# rev02_11.net
KiCad netlist of a schematic drawn in Altium Designer
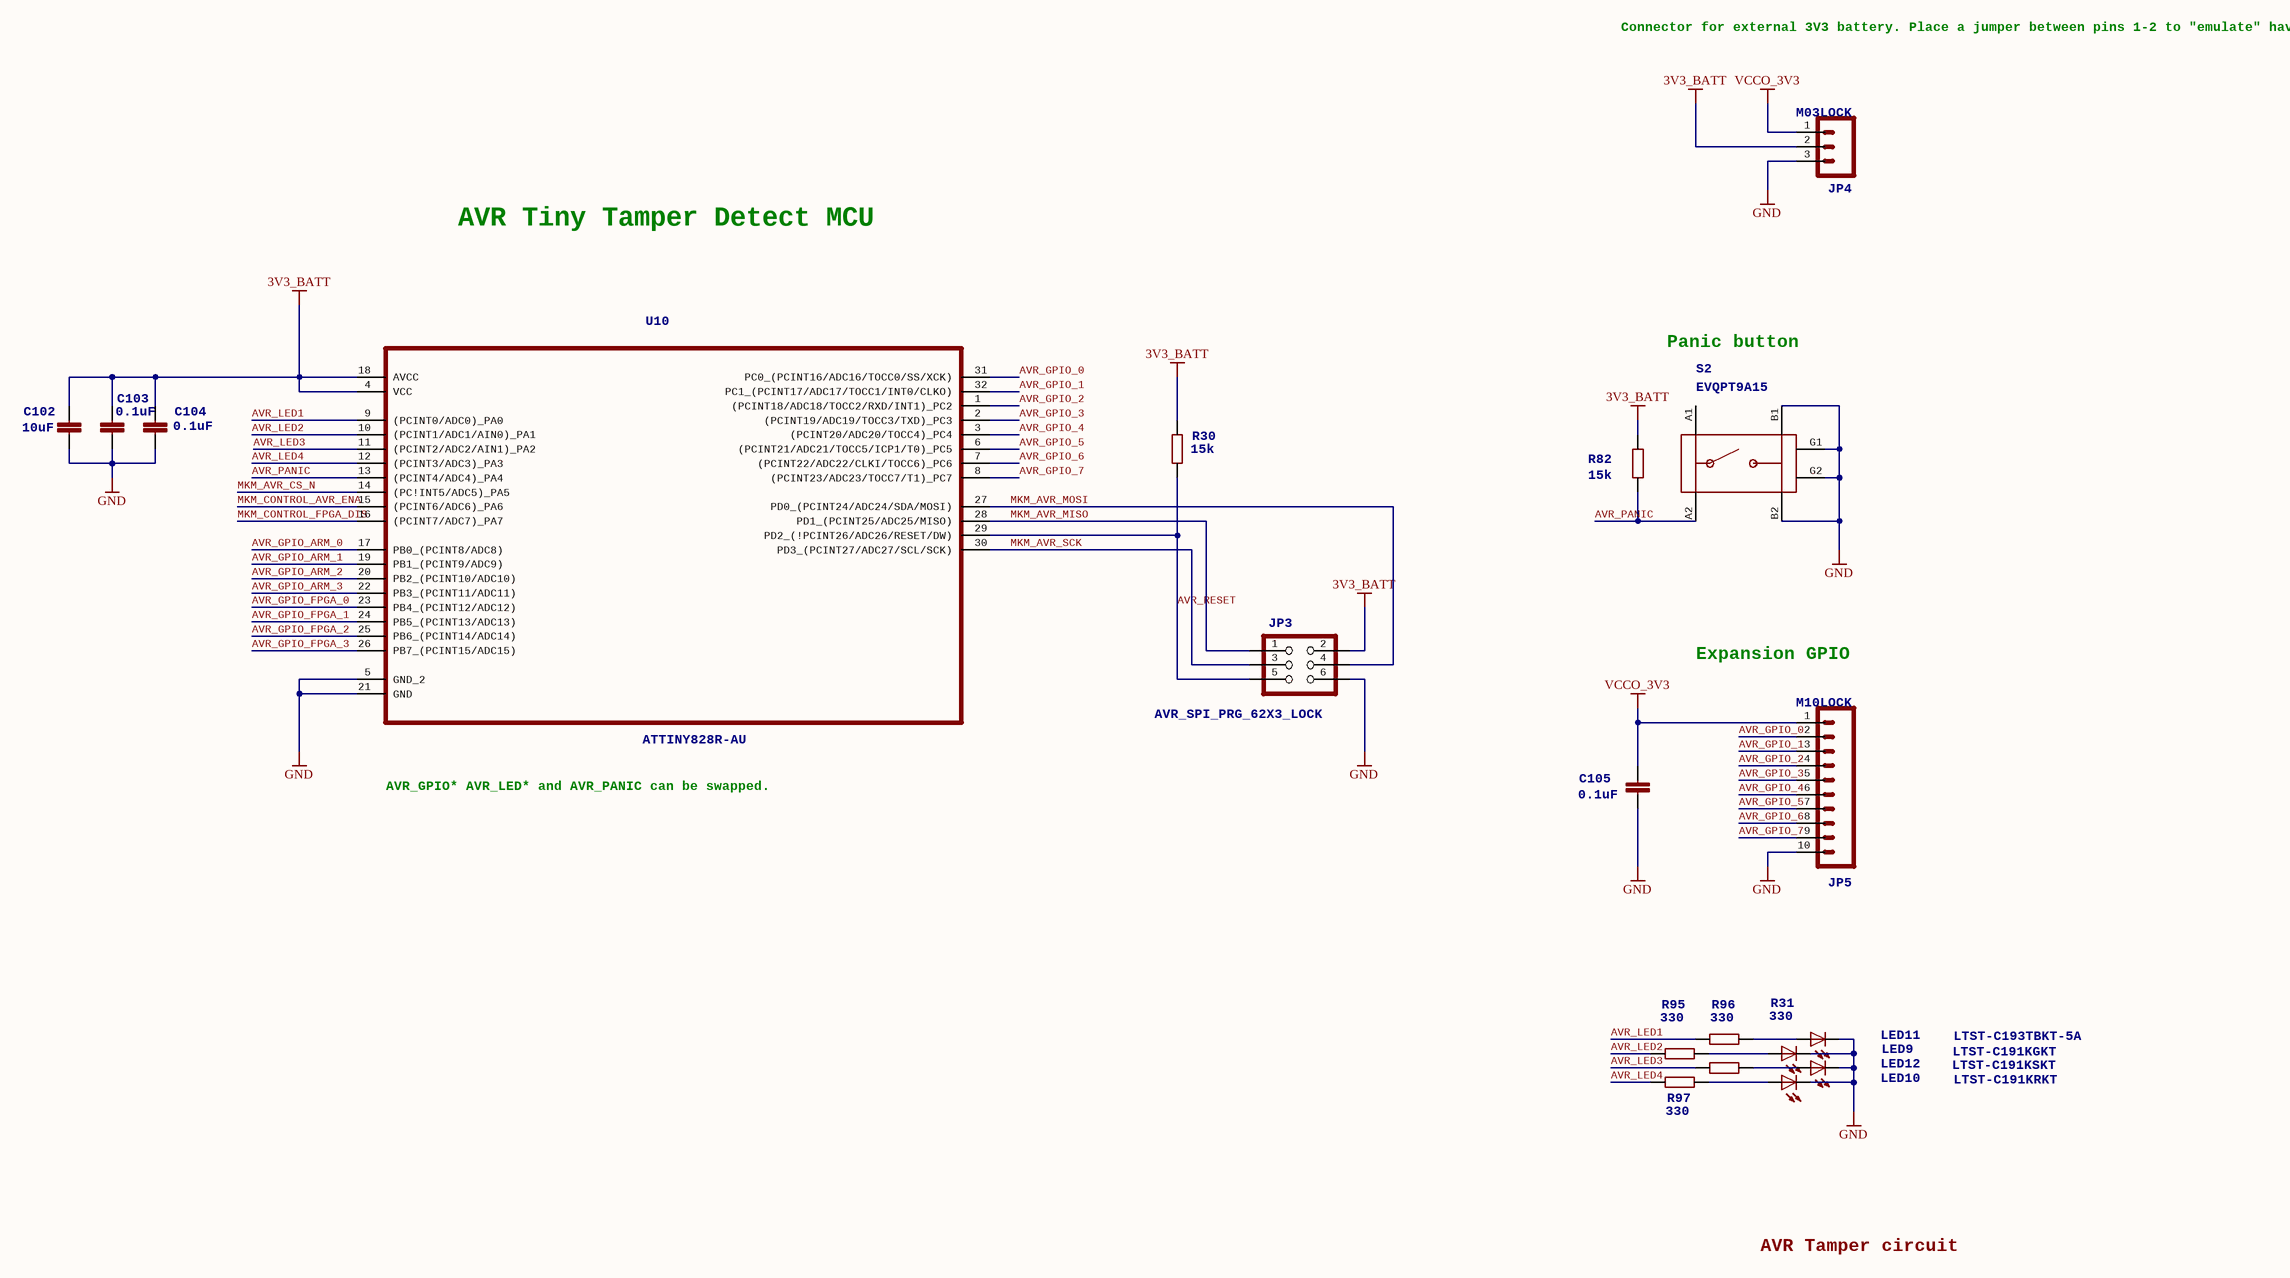
[diagram p0: rev02_11.SchDoc]

(export (version "E")
  (design (tool "Eeschema 10.0.6"))
  (components
    (comp (ref "C102")
      (value "10uF")
      (footprint "C_0805")
      (description "0805 CAPACITOR")
      (libsource (lib "resistor") (part "C-EUC0805"))
    )
    (comp (ref "C103")
      (value "0.1uF")
      (footprint "C_0402")
      (description "0402 CAPACITOR")
      (libsource (lib "resistor") (part "C-EUC0402"))
    )
    (comp (ref "C104")
      (value "0.1uF")
      (footprint "C_0402")
      (description "0402 CAPACITOR")
      (libsource (lib "resistor") (part "C-EUC0402"))
    )
    (comp (ref "C105")
      (value "0.1uF")
      (footprint "C_0402")
      (description "0402 CAPACITOR")
      (libsource (lib "resistor") (part "C-EUC0402"))
    )
    (comp (ref "JP3")
      (value "AVR_SPI_PRG_62X3_LOCK")
      (footprint "PLD-6")
      (libsource (lib "SparkFun-Connectors") (part "AVR_SPI_PRG_62X3_LOCK"))
    )
    (comp (ref "JP4")
      (value "M03LOCK")
      (footprint "PLS-3")
      (fields (field (name ">VALUE") "M03LOCK") (field (name ">NAME") "JP4"))
      (libsource (lib "SparkFun-Connectors") (part "M03LOCK"))
    )
    (comp (ref "JP5")
      (value "M10LOCK")
      (footprint "HDR1X10")
      (fields (field (name ">VALUE") "M10LOCK") (field (name ">NAME") "JP5"))
      (libsource (lib "SparkFun-Connectors") (part "M10LOCK"))
    )
    (comp (ref "LED9")
      (value "LTST-C191KGKT")
      (footprint "VD_0603")
      (description "GREEN LED")
      (libsource (lib "rev02_1") (part "LEDCHIP-LED0603"))
    )
    (comp (ref "LED10")
      (value "LTST-C191KRKT")
      (footprint "VD_0603")
      (description "RED LED")
      (libsource (lib "rev02_1") (part "LEDCHIP-LED0603"))
    )
    (comp (ref "LED11")
      (value "LTST-C193TBKT-5A")
      (footprint "VD_0603")
      (description "BLUE LED")
      (libsource (lib "rev02_1") (part "LEDCHIP-LED0603"))
    )
    (comp (ref "LED12")
      (value "LTST-C191KSKT")
      (footprint "VD_0603")
      (description "YELLOW LED")
      (libsource (lib "rev02_1") (part "LEDCHIP-LED0603"))
    )
    (comp (ref "R30")
      (value "15k")
      (footprint "R_0402")
      (description "0402 Resistor 5%")
      (fields (field (name ">NAME") "R30"))
      (libsource (lib "resistor") (part "R-EU_R0402"))
    )
    (comp (ref "R31")
      (value "330")
      (footprint "R_0402")
      (description "0402 Resistor 5%")
      (libsource (lib "resistor") (part "R-EU_R0402"))
    )
    (comp (ref "R82")
      (value "15k")
      (footprint "R_0402")
      (description "0402 Resistor 5%")
      (libsource (lib "resistor") (part "R-EU_R0402"))
    )
    (comp (ref "R95")
      (value "330")
      (footprint "R_0402")
      (description "0402 Resistor 5%")
      (libsource (lib "resistor") (part "R-EU_R0402"))
    )
    (comp (ref "R96")
      (value "330")
      (footprint "R_0402")
      (description "0402 Resistor 5%")
      (libsource (lib "resistor") (part "R-EU_R0402"))
    )
    (comp (ref "R97")
      (value "330")
      (footprint "R_0402")
      (description "0402 Resistor 5%")
      (libsource (lib "resistor") (part "R-EU_R0402"))
    )
    (comp (ref "S2")
      (value "EVQPT9A15")
      (footprint "TACTILE_SWITCH")
      (description "Tacktile switch")
      (fields (field (name ">NAME") "S2"))
      (libsource (lib "UsedComponents") (part "TACTILE_SWITCH"))
    )
    (comp (ref "U10")
      (value "ATTINY828R-AU")
      (footprint "LQFP-32")
      (description "IC, MCU, 8KB, FLASH, 20MHZ, TQFP-32")
      (fields (field (name ">NAME") "U10") (field (name ">VALUE") "ATTINY828R-AU"))
      (libsource (lib "ATMEL-ATTINY828R-AU") (part "ATTINY828R-AU"))
    )
  )
  (nets
    (net (code "1") (name "/AVR_GPIO_0") (class "Default")
      (node (ref "JP5") (pin "2") (pinfunction "2_2") (pintype "passive"))
      (node (ref "U10") (pin "31") (pinfunction "PC0_(PCINT16/ADC16/TOCC0/SS/XCK)_31") (pintype "passive"))
    )
    (net (code "2") (name "/AVR_GPIO_1") (class "Default")
      (node (ref "JP5") (pin "3") (pinfunction "3_3") (pintype "passive"))
      (node (ref "U10") (pin "32") (pinfunction "PC1_(PCINT17/ADC17/TOCC1/INT0/CLKO)_32") (pintype "passive"))
    )
    (net (code "3") (name "/AVR_GPIO_2") (class "Default")
      (node (ref "JP5") (pin "4") (pinfunction "4_4") (pintype "passive"))
      (node (ref "U10") (pin "1") (pinfunction "(PCINT18/ADC18/TOCC2/RXD/INT1)_PC2_1") (pintype "passive"))
    )
    (net (code "4") (name "/AVR_GPIO_3") (class "Default")
      (node (ref "JP5") (pin "5") (pinfunction "5_5") (pintype "passive"))
      (node (ref "U10") (pin "2") (pinfunction "(PCINT19/ADC19/TOCC3/TXD)_PC3_2") (pintype "passive"))
    )
    (net (code "5") (name "/AVR_GPIO_4") (class "Default")
      (node (ref "JP5") (pin "6") (pinfunction "6_6") (pintype "passive"))
      (node (ref "U10") (pin "3") (pinfunction "(PCINT20/ADC20/TOCC4)_PC4_3") (pintype "passive"))
    )
    (net (code "6") (name "/AVR_GPIO_5") (class "Default")
      (node (ref "JP5") (pin "7") (pinfunction "7_7") (pintype "passive"))
      (node (ref "U10") (pin "6") (pinfunction "(PCINT21/ADC21/TOCC5/ICP1/T0)_PC5_6") (pintype "passive"))
    )
    (net (code "7") (name "/AVR_GPIO_6") (class "Default")
      (node (ref "JP5") (pin "8") (pinfunction "8_8") (pintype "passive"))
      (node (ref "U10") (pin "7") (pinfunction "(PCINT22/ADC22/CLKI/TOCC6)_PC6_7") (pintype "passive"))
    )
    (net (code "8") (name "/AVR_GPIO_7") (class "Default")
      (node (ref "JP5") (pin "9") (pinfunction "9_9") (pintype "passive"))
      (node (ref "U10") (pin "8") (pinfunction "(PCINT23/ADC23/TOCC7/T1)_PC7_8") (pintype "passive"))
    )
    (net (code "9") (name "/AVR_GPIO_ARM_0") (class "Default")
      (node (ref "U10") (pin "17") (pinfunction "PB0_(PCINT8/ADC8)_17") (pintype "passive"))
    )
    (net (code "10") (name "/AVR_GPIO_ARM_1") (class "Default")
      (node (ref "U10") (pin "19") (pinfunction "PB1_(PCINT9/ADC9)_19") (pintype "passive"))
    )
    (net (code "11") (name "/AVR_GPIO_ARM_2") (class "Default")
      (node (ref "U10") (pin "20") (pinfunction "PB2_(PCINT10/ADC10)_20") (pintype "passive"))
    )
    (net (code "12") (name "/AVR_GPIO_ARM_3") (class "Default")
      (node (ref "U10") (pin "22") (pinfunction "PB3_(PCINT11/ADC11)_22") (pintype "passive"))
    )
    (net (code "13") (name "/AVR_GPIO_FPGA_0") (class "Default")
      (node (ref "U10") (pin "23") (pinfunction "PB4_(PCINT12/ADC12)_23") (pintype "passive"))
    )
    (net (code "14") (name "/AVR_GPIO_FPGA_1") (class "Default")
      (node (ref "U10") (pin "24") (pinfunction "PB5_(PCINT13/ADC13)_24") (pintype "passive"))
    )
    (net (code "15") (name "/AVR_GPIO_FPGA_2") (class "Default")
      (node (ref "U10") (pin "25") (pinfunction "PB6_(PCINT14/ADC14)_25") (pintype "passive"))
    )
    (net (code "16") (name "/AVR_GPIO_FPGA_3") (class "Default")
      (node (ref "U10") (pin "26") (pinfunction "PB7_(PCINT15/ADC15)_26") (pintype "passive"))
    )
    (net (code "17") (name "/AVR_LED1") (class "Default")
      (node (ref "R96") (pin "2") (pinfunction "2_2") (pintype "passive"))
      (node (ref "U10") (pin "9") (pinfunction "(PCINT0/ADC0)_PA0_9") (pintype "passive"))
    )
    (net (code "18") (name "/AVR_LED2") (class "Default")
      (node (ref "R95") (pin "2") (pinfunction "2_2") (pintype "passive"))
      (node (ref "U10") (pin "10") (pinfunction "(PCINT1/ADC1/AIN0)_PA1_10") (pintype "passive"))
    )
    (net (code "19") (name "/AVR_LED3") (class "Default")
      (node (ref "R31") (pin "2") (pinfunction "2_2") (pintype "passive"))
      (node (ref "U10") (pin "11") (pinfunction "(PCINT2/ADC2/AIN1)_PA2_11") (pintype "passive"))
    )
    (net (code "20") (name "/AVR_LED4") (class "Default")
      (node (ref "R97") (pin "2") (pinfunction "2_2") (pintype "passive"))
      (node (ref "U10") (pin "12") (pinfunction "(PCINT3/ADC3)_PA3_12") (pintype "passive"))
    )
    (net (code "21") (name "/AVR_PANIC") (class "Default")
      (node (ref "R82") (pin "1") (pinfunction "1_1") (pintype "passive"))
      (node (ref "S2") (pin "A2") (pinfunction "A2_A2") (pintype "passive"))
      (node (ref "U10") (pin "13") (pinfunction "(PCINT4/ADC4)_PA4_13") (pintype "passive"))
    )
    (net (code "22") (name "/AVR_RESET") (class "Default")
      (node (ref "JP3") (pin "5") (pinfunction "5_5") (pintype "passive"))
      (node (ref "R30") (pin "1") (pinfunction "1_1") (pintype "passive"))
      (node (ref "U10") (pin "29") (pinfunction "PD2_(!PCINT26/ADC26/RESET/DW)_29") (pintype "passive"))
    )
    (net (code "23") (name "/MKM_AVR_CS_N") (class "Default")
      (node (ref "U10") (pin "14") (pinfunction "(PC!INT5/ADC5)_PA5_14") (pintype "passive"))
    )
    (net (code "24") (name "/MKM_AVR_MISO") (class "Default")
      (node (ref "JP3") (pin "1") (pinfunction "1_1") (pintype "passive"))
      (node (ref "U10") (pin "28") (pinfunction "PD1_(PCINT25/ADC25/MISO)_28") (pintype "passive"))
    )
    (net (code "25") (name "/MKM_AVR_MOSI") (class "Default")
      (node (ref "JP3") (pin "4") (pinfunction "4_4") (pintype "passive"))
      (node (ref "U10") (pin "27") (pinfunction "PD0_(PCINT24/ADC24/SDA/MOSI)_27") (pintype "passive"))
    )
    (net (code "26") (name "/MKM_AVR_SCK") (class "Default")
      (node (ref "JP3") (pin "3") (pinfunction "3_3") (pintype "passive"))
      (node (ref "U10") (pin "30") (pinfunction "PD3_(PCINT27/ADC27/SCL/SCK)_30") (pintype "passive"))
    )
    (net (code "27") (name "/MKM_CONTROL_AVR_ENA") (class "Default")
      (node (ref "U10") (pin "15") (pinfunction "(PCINT6/ADC6)_PA6_15") (pintype "passive"))
    )
    (net (code "28") (name "/MKM_CONTROL_FPGA_DIS") (class "Default")
      (node (ref "U10") (pin "16") (pinfunction "(PCINT7/ADC7)_PA7_16") (pintype "passive"))
    )
    (net (code "29") (name "3V3_BATT") (class "Default")
      (node (ref "C102") (pin "1") (pinfunction "1_1") (pintype "passive"))
      (node (ref "C103") (pin "1") (pinfunction "1_1") (pintype "passive"))
      (node (ref "C104") (pin "1") (pinfunction "1_1") (pintype "passive"))
      (node (ref "JP3") (pin "2") (pinfunction "2_2") (pintype "passive"))
      (node (ref "JP4") (pin "2") (pinfunction "2_2") (pintype "passive"))
      (node (ref "R30") (pin "2") (pinfunction "2_2") (pintype "passive"))
      (node (ref "R82") (pin "2") (pinfunction "2_2") (pintype "passive"))
      (node (ref "U10") (pin "18") (pinfunction "AVCC_18") (pintype "power_in"))
      (node (ref "U10") (pin "4") (pinfunction "VCC_4") (pintype "power_in"))
    )
    (net (code "30") (name "GND") (class "Default")
      (node (ref "C102") (pin "2") (pinfunction "2_2") (pintype "passive"))
      (node (ref "C103") (pin "2") (pinfunction "2_2") (pintype "passive"))
      (node (ref "C104") (pin "2") (pinfunction "2_2") (pintype "passive"))
      (node (ref "C105") (pin "2") (pinfunction "2_2") (pintype "passive"))
      (node (ref "JP3") (pin "6") (pinfunction "6_6") (pintype "passive"))
      (node (ref "JP4") (pin "3") (pinfunction "3_3") (pintype "passive"))
      (node (ref "JP5") (pin "10") (pinfunction "10_10") (pintype "passive"))
      (node (ref "LED10") (pin "2") (pinfunction "C_2") (pintype "passive"))
      (node (ref "LED11") (pin "2") (pinfunction "C_2") (pintype "passive"))
      (node (ref "LED12") (pin "2") (pinfunction "C_2") (pintype "passive"))
      (node (ref "LED9") (pin "2") (pinfunction "C_2") (pintype "passive"))
      (node (ref "S2") (pin "B1") (pinfunction "B1_B1") (pintype "passive"))
      (node (ref "S2") (pin "B2") (pinfunction "B2_B2") (pintype "passive"))
      (node (ref "S2") (pin "G1") (pinfunction "G1_G1") (pintype "power_in"))
      (node (ref "S2") (pin "G2") (pinfunction "G2_G2") (pintype "power_in"))
      (node (ref "U10") (pin "21") (pinfunction "GND_21") (pintype "passive"))
      (node (ref "U10") (pin "5") (pinfunction "GND_2_5") (pintype "passive"))
    )
    (net (code "31") (name "Net-(LED9-A)") (class "Default")
      (node (ref "LED9") (pin "1") (pinfunction "A_1") (pintype "passive"))
      (node (ref "R95") (pin "1") (pinfunction "1_1") (pintype "passive"))
    )
    (net (code "32") (name "Net-(LED10-A)") (class "Default")
      (node (ref "LED10") (pin "1") (pinfunction "A_1") (pintype "passive"))
      (node (ref "R97") (pin "1") (pinfunction "1_1") (pintype "passive"))
    )
    (net (code "33") (name "Net-(LED11-A)") (class "Default")
      (node (ref "LED11") (pin "1") (pinfunction "A_1") (pintype "passive"))
      (node (ref "R96") (pin "1") (pinfunction "1_1") (pintype "passive"))
    )
    (net (code "34") (name "Net-(LED12-A)") (class "Default")
      (node (ref "LED12") (pin "1") (pinfunction "A_1") (pintype "passive"))
      (node (ref "R31") (pin "1") (pinfunction "1_1") (pintype "passive"))
    )
    (net (code "35") (name "VCCO_3V3") (class "Default")
      (node (ref "C105") (pin "1") (pinfunction "1_1") (pintype "passive"))
      (node (ref "JP4") (pin "1") (pinfunction "1_1") (pintype "passive"))
      (node (ref "JP5") (pin "1") (pinfunction "1_1") (pintype "passive"))
    )
    (net (code "36") (name "unconnected-(S2-PadA1)") (class "Default")
      (node (ref "S2") (pin "A1") (pinfunction "A1_A1") (pintype "passive"))
    )
  )
)
